# AppleMouse_old.net
KiCad netlist of a schematic drawn in EAGLE
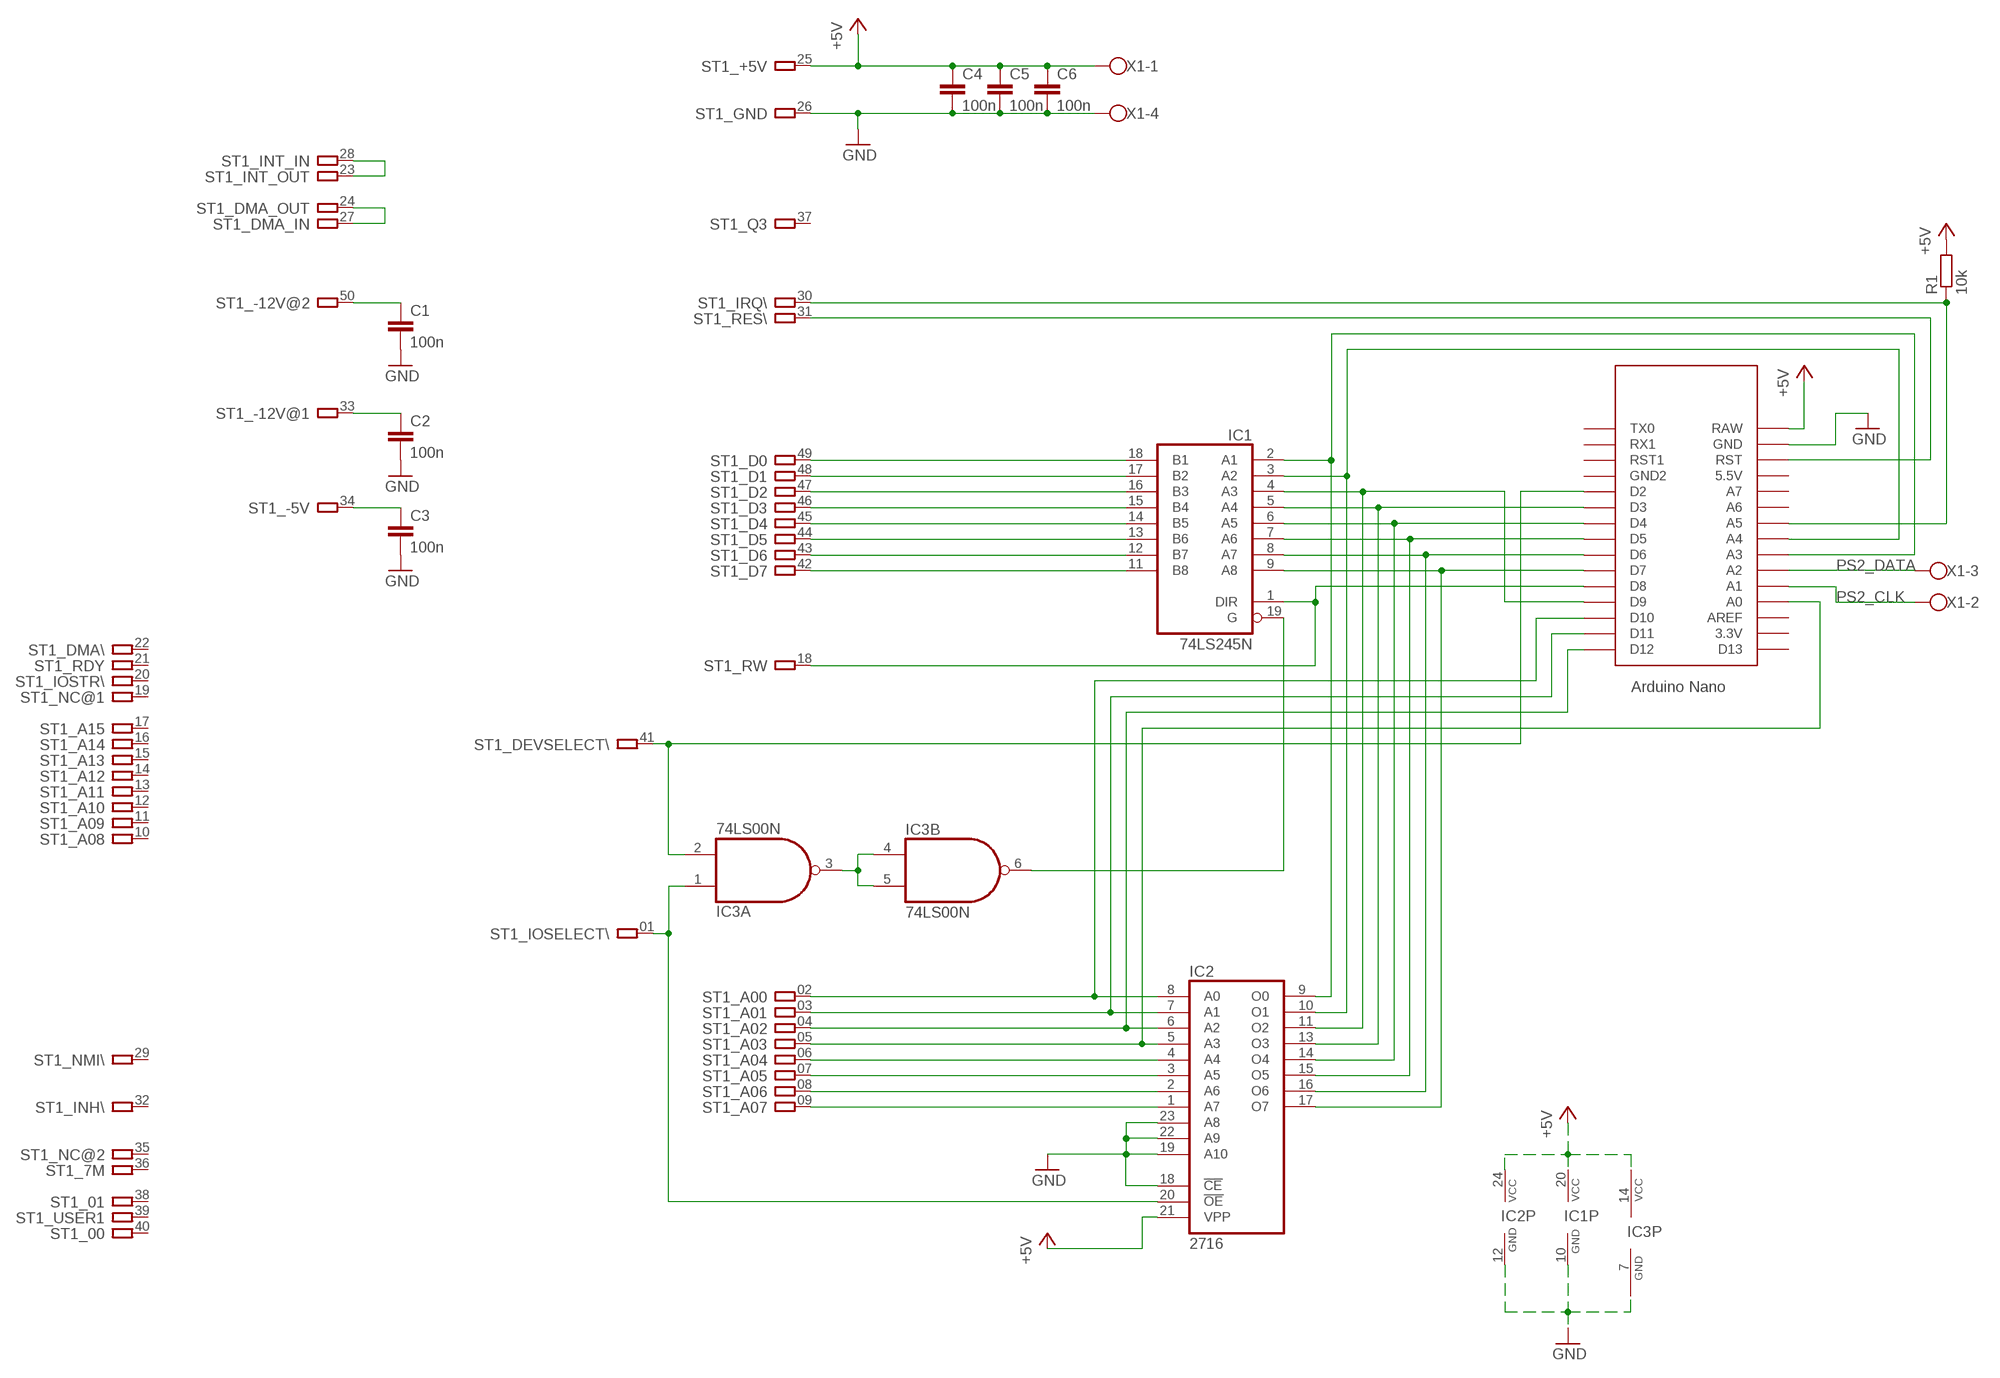
[diagram p0: schematic, sheet 1]

(export (version "E")
  (design (tool "Eeschema 10.0.6"))
  (components
    (comp (ref "C1")
      (value "100n")
      (footprint "eagle-import:C025-030X050")
      (libsource (lib "eagle-import") (part "C-EU025-030X050"))
    )
    (comp (ref "C2")
      (value "100n")
      (footprint "eagle-import:C025-030X050")
      (libsource (lib "eagle-import") (part "C-EU025-030X050"))
    )
    (comp (ref "C3")
      (value "100n")
      (footprint "eagle-import:C025-030X050")
      (libsource (lib "eagle-import") (part "C-EU025-030X050"))
    )
    (comp (ref "C4")
      (value "100n")
      (footprint "eagle-import:C025-030X050")
      (libsource (lib "eagle-import") (part "C-EU025-030X050"))
    )
    (comp (ref "C5")
      (value "100n")
      (footprint "eagle-import:C025-030X050")
      (libsource (lib "eagle-import") (part "C-EU025-030X050"))
    )
    (comp (ref "C6")
      (value "100n")
      (footprint "eagle-import:C025-030X050")
      (libsource (lib "eagle-import") (part "C-EU025-030X050"))
    )
    (comp (ref "IC1")
      (value "74LS245N")
      (footprint "eagle-import:DIL20")
      (libsource (lib "eagle-import") (part "74245NLS"))
    )
    (comp (ref "IC2")
      (value "2716")
      (footprint "eagle-import:DIL24")
      (libsource (lib "eagle-import") (part "2716"))
    )
    (comp (ref "IC3")
      (value "74LS00N")
      (footprint "eagle-import:DIL14")
      (libsource (lib "eagle-import") (part "7400NLS"))
    )
    (comp (ref "R1")
      (value "10k")
      (footprint "eagle-import:0204_7")
      (libsource (lib "eagle-import") (part "R-EU_0204/7"))
    )
    (comp (ref "ST1")
      (value "A2-50PINSLOT1-3")
      (footprint "eagle-import:A2-50PIN-SL1-3")
      (libsource (lib "eagle-import") (part "A2-50PINSLOT1-3"))
    )
    (comp (ref "U$1")
      (value "NANO")
      (footprint "eagle-import:NANO")
      (libsource (lib "eagle-import") (part "NANO"))
    )
    (comp (ref "X1")
      (value "W237-4")
      (footprint "eagle-import:W237-4")
      (libsource (lib "eagle-import") (part "W237-4"))
    )
  )
  (nets
    (net (code "1") (name "+5V") (class "Default")
      (node (ref "C4") (pin "1") (pinfunction "1_1") (pintype "passive"))
      (node (ref "C5") (pin "1") (pinfunction "1_1") (pintype "passive"))
      (node (ref "C6") (pin "1") (pinfunction "1_1") (pintype "passive"))
      (node (ref "IC1") (pin "20") (pinfunction "VCC_20") (pintype "power_in"))
      (node (ref "IC2") (pin "21") (pinfunction "VPP_21") (pintype "input"))
      (node (ref "IC2") (pin "24") (pinfunction "VCC_24") (pintype "power_in"))
      (node (ref "IC3") (pin "14") (pinfunction "VCC_14") (pintype "power_in"))
      (node (ref "R1") (pin "2") (pinfunction "2_2") (pintype "passive"))
      (node (ref "ST1") (pin "25") (pinfunction "P_25") (pintype "bidirectional"))
      (node (ref "U$1") (pin "RAW") (pinfunction "RAW_RAW") (pintype "bidirectional"))
      (node (ref "X1") (pin "1") (pinfunction "KL_1") (pintype "passive"))
    )
    (net (code "2") (name "/PS2_CLK") (class "Default")
      (node (ref "U$1") (pin "A1") (pinfunction "A1_A1") (pintype "bidirectional"))
      (node (ref "X1") (pin "2") (pinfunction "KL_2") (pintype "passive"))
    )
    (net (code "3") (name "/PS2_DATA") (class "Default")
      (node (ref "U$1") (pin "A2") (pinfunction "A2_A2") (pintype "bidirectional"))
      (node (ref "X1") (pin "3") (pinfunction "KL_3") (pintype "passive"))
    )
    (net (code "4") (name "GND") (class "Default")
      (node (ref "C1") (pin "2") (pinfunction "2_2") (pintype "passive"))
      (node (ref "C2") (pin "2") (pinfunction "2_2") (pintype "passive"))
      (node (ref "C3") (pin "2") (pinfunction "2_2") (pintype "passive"))
      (node (ref "C4") (pin "2") (pinfunction "2_2") (pintype "passive"))
      (node (ref "C5") (pin "2") (pinfunction "2_2") (pintype "passive"))
      (node (ref "C6") (pin "2") (pinfunction "2_2") (pintype "passive"))
      (node (ref "IC1") (pin "10") (pinfunction "GND_10") (pintype "power_in"))
      (node (ref "IC2") (pin "12") (pinfunction "GND_12") (pintype "power_in"))
      (node (ref "IC2") (pin "18") (pinfunction "~{CE}_18") (pintype "input"))
      (node (ref "IC2") (pin "19") (pinfunction "A10_19") (pintype "input"))
      (node (ref "IC2") (pin "22") (pinfunction "A9_22") (pintype "input"))
      (node (ref "IC2") (pin "23") (pinfunction "A8_23") (pintype "input"))
      (node (ref "IC3") (pin "7") (pinfunction "GND_7") (pintype "power_in"))
      (node (ref "ST1") (pin "26") (pinfunction "P_26") (pintype "bidirectional"))
      (node (ref "U$1") (pin "GND") (pinfunction "GND_GND") (pintype "bidirectional"))
      (node (ref "X1") (pin "4") (pinfunction "KL_4") (pintype "passive"))
    )
    (net (code "5") (name "Net-(IC1A-A1)") (class "Default")
      (node (ref "IC1") (pin "2") (pinfunction "A1_2") (pintype "bidirectional"))
      (node (ref "IC2") (pin "9") (pinfunction "O0_9") (pintype "tri_state"))
      (node (ref "U$1") (pin "A3") (pinfunction "A3_A3") (pintype "bidirectional"))
    )
    (net (code "6") (name "Net-(IC1A-A2)") (class "Default")
      (node (ref "IC1") (pin "3") (pinfunction "A2_3") (pintype "bidirectional"))
      (node (ref "IC2") (pin "10") (pinfunction "O1_10") (pintype "tri_state"))
      (node (ref "U$1") (pin "A4") (pinfunction "A4_A4") (pintype "bidirectional"))
    )
    (net (code "7") (name "Net-(IC1A-A3)") (class "Default")
      (node (ref "IC1") (pin "4") (pinfunction "A3_4") (pintype "bidirectional"))
      (node (ref "IC2") (pin "11") (pinfunction "O2_11") (pintype "tri_state"))
      (node (ref "U$1") (pin "D9") (pinfunction "D9_D9") (pintype "bidirectional"))
    )
    (net (code "8") (name "Net-(IC1A-A4)") (class "Default")
      (node (ref "IC1") (pin "5") (pinfunction "A4_5") (pintype "bidirectional"))
      (node (ref "IC2") (pin "13") (pinfunction "O3_13") (pintype "tri_state"))
      (node (ref "U$1") (pin "D3") (pinfunction "D3_D3") (pintype "bidirectional"))
    )
    (net (code "9") (name "Net-(IC1A-A5)") (class "Default")
      (node (ref "IC1") (pin "6") (pinfunction "A5_6") (pintype "bidirectional"))
      (node (ref "IC2") (pin "14") (pinfunction "O4_14") (pintype "tri_state"))
      (node (ref "U$1") (pin "D4") (pinfunction "D4_D4") (pintype "bidirectional"))
    )
    (net (code "10") (name "Net-(IC1A-A6)") (class "Default")
      (node (ref "IC1") (pin "7") (pinfunction "A6_7") (pintype "bidirectional"))
      (node (ref "IC2") (pin "15") (pinfunction "O5_15") (pintype "tri_state"))
      (node (ref "U$1") (pin "D5") (pinfunction "D5_D5") (pintype "bidirectional"))
    )
    (net (code "11") (name "Net-(IC1A-A7)") (class "Default")
      (node (ref "IC1") (pin "8") (pinfunction "A7_8") (pintype "bidirectional"))
      (node (ref "IC2") (pin "16") (pinfunction "O6_16") (pintype "tri_state"))
      (node (ref "U$1") (pin "D6") (pinfunction "D6_D6") (pintype "bidirectional"))
    )
    (net (code "12") (name "Net-(IC1A-A8)") (class "Default")
      (node (ref "IC1") (pin "9") (pinfunction "A8_9") (pintype "bidirectional"))
      (node (ref "IC2") (pin "17") (pinfunction "O7_17") (pintype "tri_state"))
      (node (ref "U$1") (pin "D7") (pinfunction "D7_D7") (pintype "bidirectional"))
    )
    (net (code "13") (name "Net-(IC1A-B1)") (class "Default")
      (node (ref "IC1") (pin "18") (pinfunction "B1_18") (pintype "bidirectional"))
      (node (ref "ST1") (pin "49") (pinfunction "P_49") (pintype "bidirectional"))
    )
    (net (code "14") (name "Net-(IC1A-B2)") (class "Default")
      (node (ref "IC1") (pin "17") (pinfunction "B2_17") (pintype "bidirectional"))
      (node (ref "ST1") (pin "48") (pinfunction "P_48") (pintype "bidirectional"))
    )
    (net (code "15") (name "Net-(IC1A-B3)") (class "Default")
      (node (ref "IC1") (pin "16") (pinfunction "B3_16") (pintype "bidirectional"))
      (node (ref "ST1") (pin "47") (pinfunction "P_47") (pintype "bidirectional"))
    )
    (net (code "16") (name "Net-(IC1A-B4)") (class "Default")
      (node (ref "IC1") (pin "15") (pinfunction "B4_15") (pintype "bidirectional"))
      (node (ref "ST1") (pin "46") (pinfunction "P_46") (pintype "bidirectional"))
    )
    (net (code "17") (name "Net-(IC1A-B5)") (class "Default")
      (node (ref "IC1") (pin "14") (pinfunction "B5_14") (pintype "bidirectional"))
      (node (ref "ST1") (pin "45") (pinfunction "P_45") (pintype "bidirectional"))
    )
    (net (code "18") (name "Net-(IC1A-B6)") (class "Default")
      (node (ref "IC1") (pin "13") (pinfunction "B6_13") (pintype "bidirectional"))
      (node (ref "ST1") (pin "44") (pinfunction "P_44") (pintype "bidirectional"))
    )
    (net (code "19") (name "Net-(IC1A-B7)") (class "Default")
      (node (ref "IC1") (pin "12") (pinfunction "B7_12") (pintype "bidirectional"))
      (node (ref "ST1") (pin "43") (pinfunction "P_43") (pintype "bidirectional"))
    )
    (net (code "20") (name "Net-(IC1A-B8)") (class "Default")
      (node (ref "IC1") (pin "11") (pinfunction "B8_11") (pintype "bidirectional"))
      (node (ref "ST1") (pin "42") (pinfunction "P_42") (pintype "bidirectional"))
    )
    (net (code "21") (name "Net-(IC1A-DIR)") (class "Default")
      (node (ref "IC1") (pin "1") (pinfunction "DIR_1") (pintype "input"))
      (node (ref "ST1") (pin "18") (pinfunction "P_18") (pintype "bidirectional"))
      (node (ref "U$1") (pin "D8") (pinfunction "D8_D8") (pintype "bidirectional"))
    )
    (net (code "22") (name "Net-(IC1A-G)") (class "Default")
      (node (ref "IC1") (pin "19") (pinfunction "G_19") (pintype "input"))
      (node (ref "IC3") (pin "6") (pinfunction "O_6") (pintype "output"))
    )
    (net (code "23") (name "Net-(IC2A-A0)") (class "Default")
      (node (ref "IC2") (pin "8") (pinfunction "A0_8") (pintype "input"))
      (node (ref "ST1") (pin "02") (pinfunction "P_02") (pintype "bidirectional"))
      (node (ref "U$1") (pin "D10") (pinfunction "D10_D10") (pintype "bidirectional"))
    )
    (net (code "24") (name "Net-(IC2A-A1)") (class "Default")
      (node (ref "IC2") (pin "7") (pinfunction "A1_7") (pintype "input"))
      (node (ref "ST1") (pin "03") (pinfunction "P_03") (pintype "bidirectional"))
      (node (ref "U$1") (pin "D11") (pinfunction "D11_D11") (pintype "bidirectional"))
    )
    (net (code "25") (name "Net-(IC2A-A2)") (class "Default")
      (node (ref "IC2") (pin "6") (pinfunction "A2_6") (pintype "input"))
      (node (ref "ST1") (pin "04") (pinfunction "P_04") (pintype "bidirectional"))
      (node (ref "U$1") (pin "D12") (pinfunction "D12_D12") (pintype "bidirectional"))
    )
    (net (code "26") (name "Net-(IC2A-A3)") (class "Default")
      (node (ref "IC2") (pin "5") (pinfunction "A3_5") (pintype "input"))
      (node (ref "ST1") (pin "05") (pinfunction "P_05") (pintype "bidirectional"))
      (node (ref "U$1") (pin "A0") (pinfunction "A0_A0") (pintype "bidirectional"))
    )
    (net (code "27") (name "Net-(IC2A-A4)") (class "Default")
      (node (ref "IC2") (pin "4") (pinfunction "A4_4") (pintype "input"))
      (node (ref "ST1") (pin "06") (pinfunction "P_06") (pintype "bidirectional"))
    )
    (net (code "28") (name "Net-(IC2A-A5)") (class "Default")
      (node (ref "IC2") (pin "3") (pinfunction "A5_3") (pintype "input"))
      (node (ref "ST1") (pin "07") (pinfunction "P_07") (pintype "bidirectional"))
    )
    (net (code "29") (name "Net-(IC2A-A6)") (class "Default")
      (node (ref "IC2") (pin "2") (pinfunction "A6_2") (pintype "input"))
      (node (ref "ST1") (pin "08") (pinfunction "P_08") (pintype "bidirectional"))
    )
    (net (code "30") (name "Net-(IC2A-A7)") (class "Default")
      (node (ref "IC2") (pin "1") (pinfunction "A7_1") (pintype "input"))
      (node (ref "ST1") (pin "09") (pinfunction "P_09") (pintype "bidirectional"))
    )
    (net (code "31") (name "Net-(IC2A-~{OE})") (class "Default")
      (node (ref "IC2") (pin "20") (pinfunction "~{OE}_20") (pintype "input"))
      (node (ref "IC3") (pin "1") (pinfunction "I0_1") (pintype "input"))
      (node (ref "ST1") (pin "01") (pinfunction "P_01") (pintype "bidirectional"))
    )
    (net (code "32") (name "Net-(IC3A-I1)") (class "Default")
      (node (ref "IC3") (pin "2") (pinfunction "I1_2") (pintype "input"))
      (node (ref "ST1") (pin "41") (pinfunction "P_41") (pintype "bidirectional"))
      (node (ref "U$1") (pin "D2") (pinfunction "D2_D2") (pintype "bidirectional"))
    )
    (net (code "33") (name "Net-(IC3A-O)") (class "Default")
      (node (ref "IC3") (pin "3") (pinfunction "O_3") (pintype "output"))
      (node (ref "IC3") (pin "4") (pinfunction "I0_4") (pintype "input"))
      (node (ref "IC3") (pin "5") (pinfunction "I1_5") (pintype "input"))
    )
    (net (code "34") (name "Net-(ST1AH-P)") (class "Default")
      (node (ref "ST1") (pin "24") (pinfunction "P_24") (pintype "bidirectional"))
      (node (ref "ST1") (pin "27") (pinfunction "P_27") (pintype "bidirectional"))
    )
    (net (code "35") (name "Net-(ST1AL-P)") (class "Default")
      (node (ref "ST1") (pin "23") (pinfunction "P_23") (pintype "bidirectional"))
      (node (ref "ST1") (pin "28") (pinfunction "P_28") (pintype "bidirectional"))
    )
    (net (code "36") (name "Net-(ST1AP-P)") (class "Default")
      (node (ref "R1") (pin "1") (pinfunction "1_1") (pintype "passive"))
      (node (ref "ST1") (pin "30") (pinfunction "P_30") (pintype "bidirectional"))
      (node (ref "U$1") (pin "A5") (pinfunction "A5_A5") (pintype "bidirectional"))
    )
    (net (code "37") (name "Net-(ST1AV-P)") (class "Default")
      (node (ref "ST1") (pin "31") (pinfunction "P_31") (pintype "bidirectional"))
      (node (ref "U$1") (pin "RST") (pinfunction "RST_RST") (pintype "bidirectional"))
    )
    (net (code "38") (name "Net-(ST1B-P)") (class "Default")
      (node (ref "C2") (pin "1") (pinfunction "1_1") (pintype "passive"))
      (node (ref "ST1") (pin "33") (pinfunction "P_33") (pintype "bidirectional"))
    )
    (net (code "39") (name "Net-(ST1C-P)") (class "Default")
      (node (ref "C1") (pin "1") (pinfunction "1_1") (pintype "passive"))
      (node (ref "ST1") (pin "50") (pinfunction "P_50") (pintype "bidirectional"))
    )
    (net (code "40") (name "Net-(ST1D-P)") (class "Default")
      (node (ref "C3") (pin "1") (pinfunction "1_1") (pintype "passive"))
      (node (ref "ST1") (pin "34") (pinfunction "P_34") (pintype "bidirectional"))
    )
    (net (code "41") (name "unconnected-(ST1AG-P-Pad22)") (class "Default")
      (node (ref "ST1") (pin "22") (pinfunction "P_22") (pintype "bidirectional"))
    )
    (net (code "42") (name "unconnected-(ST1AK-P-Pad32)") (class "Default")
      (node (ref "ST1") (pin "32") (pinfunction "P_32") (pintype "bidirectional"))
    )
    (net (code "43") (name "unconnected-(ST1AO-P-Pad20)") (class "Default")
      (node (ref "ST1") (pin "20") (pinfunction "P_20") (pintype "bidirectional"))
    )
    (net (code "44") (name "unconnected-(ST1AQ-P-Pad19)") (class "Default")
      (node (ref "ST1") (pin "19") (pinfunction "P_19") (pintype "bidirectional"))
    )
    (net (code "45") (name "unconnected-(ST1AR-P-Pad35)") (class "Default")
      (node (ref "ST1") (pin "35") (pinfunction "P_35") (pintype "bidirectional"))
    )
    (net (code "46") (name "unconnected-(ST1AS-P-Pad29)") (class "Default")
      (node (ref "ST1") (pin "29") (pinfunction "P_29") (pintype "bidirectional"))
    )
    (net (code "47") (name "unconnected-(ST1AT-P-Pad37)") (class "Default")
      (node (ref "ST1") (pin "37") (pinfunction "P_37") (pintype "bidirectional"))
    )
    (net (code "48") (name "unconnected-(ST1AU-P-Pad21)") (class "Default")
      (node (ref "ST1") (pin "21") (pinfunction "P_21") (pintype "bidirectional"))
    )
    (net (code "49") (name "unconnected-(ST1AX-P-Pad39)") (class "Default")
      (node (ref "ST1") (pin "39") (pinfunction "P_39") (pintype "bidirectional"))
    )
    (net (code "50") (name "unconnected-(ST1E-P-Pad40)") (class "Default")
      (node (ref "ST1") (pin "40") (pinfunction "P_40") (pintype "bidirectional"))
    )
    (net (code "51") (name "unconnected-(ST1F-P-Pad38)") (class "Default")
      (node (ref "ST1") (pin "38") (pinfunction "P_38") (pintype "bidirectional"))
    )
    (net (code "52") (name "unconnected-(ST1G-P-Pad36)") (class "Default")
      (node (ref "ST1") (pin "36") (pinfunction "P_36") (pintype "bidirectional"))
    )
    (net (code "53") (name "unconnected-(ST1P-P-Pad10)") (class "Default")
      (node (ref "ST1") (pin "10") (pinfunction "P_10") (pintype "bidirectional"))
    )
    (net (code "54") (name "unconnected-(ST1Q-P-Pad11)") (class "Default")
      (node (ref "ST1") (pin "11") (pinfunction "P_11") (pintype "bidirectional"))
    )
    (net (code "55") (name "unconnected-(ST1R-P-Pad12)") (class "Default")
      (node (ref "ST1") (pin "12") (pinfunction "P_12") (pintype "bidirectional"))
    )
    (net (code "56") (name "unconnected-(ST1S-P-Pad13)") (class "Default")
      (node (ref "ST1") (pin "13") (pinfunction "P_13") (pintype "bidirectional"))
    )
    (net (code "57") (name "unconnected-(ST1T-P-Pad14)") (class "Default")
      (node (ref "ST1") (pin "14") (pinfunction "P_14") (pintype "bidirectional"))
    )
    (net (code "58") (name "unconnected-(ST1U-P-Pad15)") (class "Default")
      (node (ref "ST1") (pin "15") (pinfunction "P_15") (pintype "bidirectional"))
    )
    (net (code "59") (name "unconnected-(ST1V-P-Pad16)") (class "Default")
      (node (ref "ST1") (pin "16") (pinfunction "P_16") (pintype "bidirectional"))
    )
    (net (code "60") (name "unconnected-(ST1W-P-Pad17)") (class "Default")
      (node (ref "ST1") (pin "17") (pinfunction "P_17") (pintype "bidirectional"))
    )
    (net (code "61") (name "unconnected-(U$1-5.5V-Pad5V)") (class "Default")
      (node (ref "U$1") (pin "5V") (pinfunction "5.5V_5V") (pintype "bidirectional"))
    )
    (net (code "62") (name "unconnected-(U$1-GND2-PadGND1)") (class "Default")
      (node (ref "U$1") (pin "GND1") (pinfunction "GND2_GND1") (pintype "bidirectional"))
    )
    (net (code "63") (name "unconnected-(U$1-Pad3.3V)") (class "Default")
      (node (ref "U$1") (pin "3.3V") (pinfunction "3.3V_3.3V") (pintype "bidirectional"))
    )
    (net (code "64") (name "unconnected-(U$1-PadA6)") (class "Default")
      (node (ref "U$1") (pin "A6") (pinfunction "A6_A6") (pintype "bidirectional"))
    )
    (net (code "65") (name "unconnected-(U$1-PadA7)") (class "Default")
      (node (ref "U$1") (pin "A7") (pinfunction "A7_A7") (pintype "bidirectional"))
    )
    (net (code "66") (name "unconnected-(U$1-PadAREF)") (class "Default")
      (node (ref "U$1") (pin "AREF") (pinfunction "AREF_AREF") (pintype "bidirectional"))
    )
    (net (code "67") (name "unconnected-(U$1-PadD13)") (class "Default")
      (node (ref "U$1") (pin "D13") (pinfunction "D13_D13") (pintype "bidirectional"))
    )
    (net (code "68") (name "unconnected-(U$1-PadICSP1)") (class "Default")
      (node (ref "U$1") (pin "ICSP1") (pinfunction "ICSP1_ICSP1") (pintype "bidirectional"))
    )
    (net (code "69") (name "unconnected-(U$1-PadICSP2)") (class "Default")
      (node (ref "U$1") (pin "ICSP2") (pinfunction "ICSP2_ICSP2") (pintype "bidirectional"))
    )
    (net (code "70") (name "unconnected-(U$1-PadICSP3)") (class "Default")
      (node (ref "U$1") (pin "ICSP3") (pinfunction "ICSP3_ICSP3") (pintype "bidirectional"))
    )
    (net (code "71") (name "unconnected-(U$1-PadICSP4)") (class "Default")
      (node (ref "U$1") (pin "ICSP4") (pinfunction "ICSP4_ICSP4") (pintype "bidirectional"))
    )
    (net (code "72") (name "unconnected-(U$1-PadICSP5)") (class "Default")
      (node (ref "U$1") (pin "ICSP5") (pinfunction "ICSP5_ICSP5") (pintype "bidirectional"))
    )
    (net (code "73") (name "unconnected-(U$1-PadICSP6)") (class "Default")
      (node (ref "U$1") (pin "ICSP6") (pinfunction "ICSP6_ICSP6") (pintype "bidirectional"))
    )
    (net (code "74") (name "unconnected-(U$1-PadRST1)") (class "Default")
      (node (ref "U$1") (pin "RST1") (pinfunction "RST1_RST1") (pintype "bidirectional"))
    )
    (net (code "75") (name "unconnected-(U$1-PadRX1)") (class "Default")
      (node (ref "U$1") (pin "RX1") (pinfunction "RX1_RX1") (pintype "bidirectional"))
    )
    (net (code "76") (name "unconnected-(U$1-PadTX0)") (class "Default")
      (node (ref "U$1") (pin "TX0") (pinfunction "TX0_TX0") (pintype "bidirectional"))
    )
  )
)
